# 01A-005.net
KiCad netlist of a schematic drawn in EAGLE
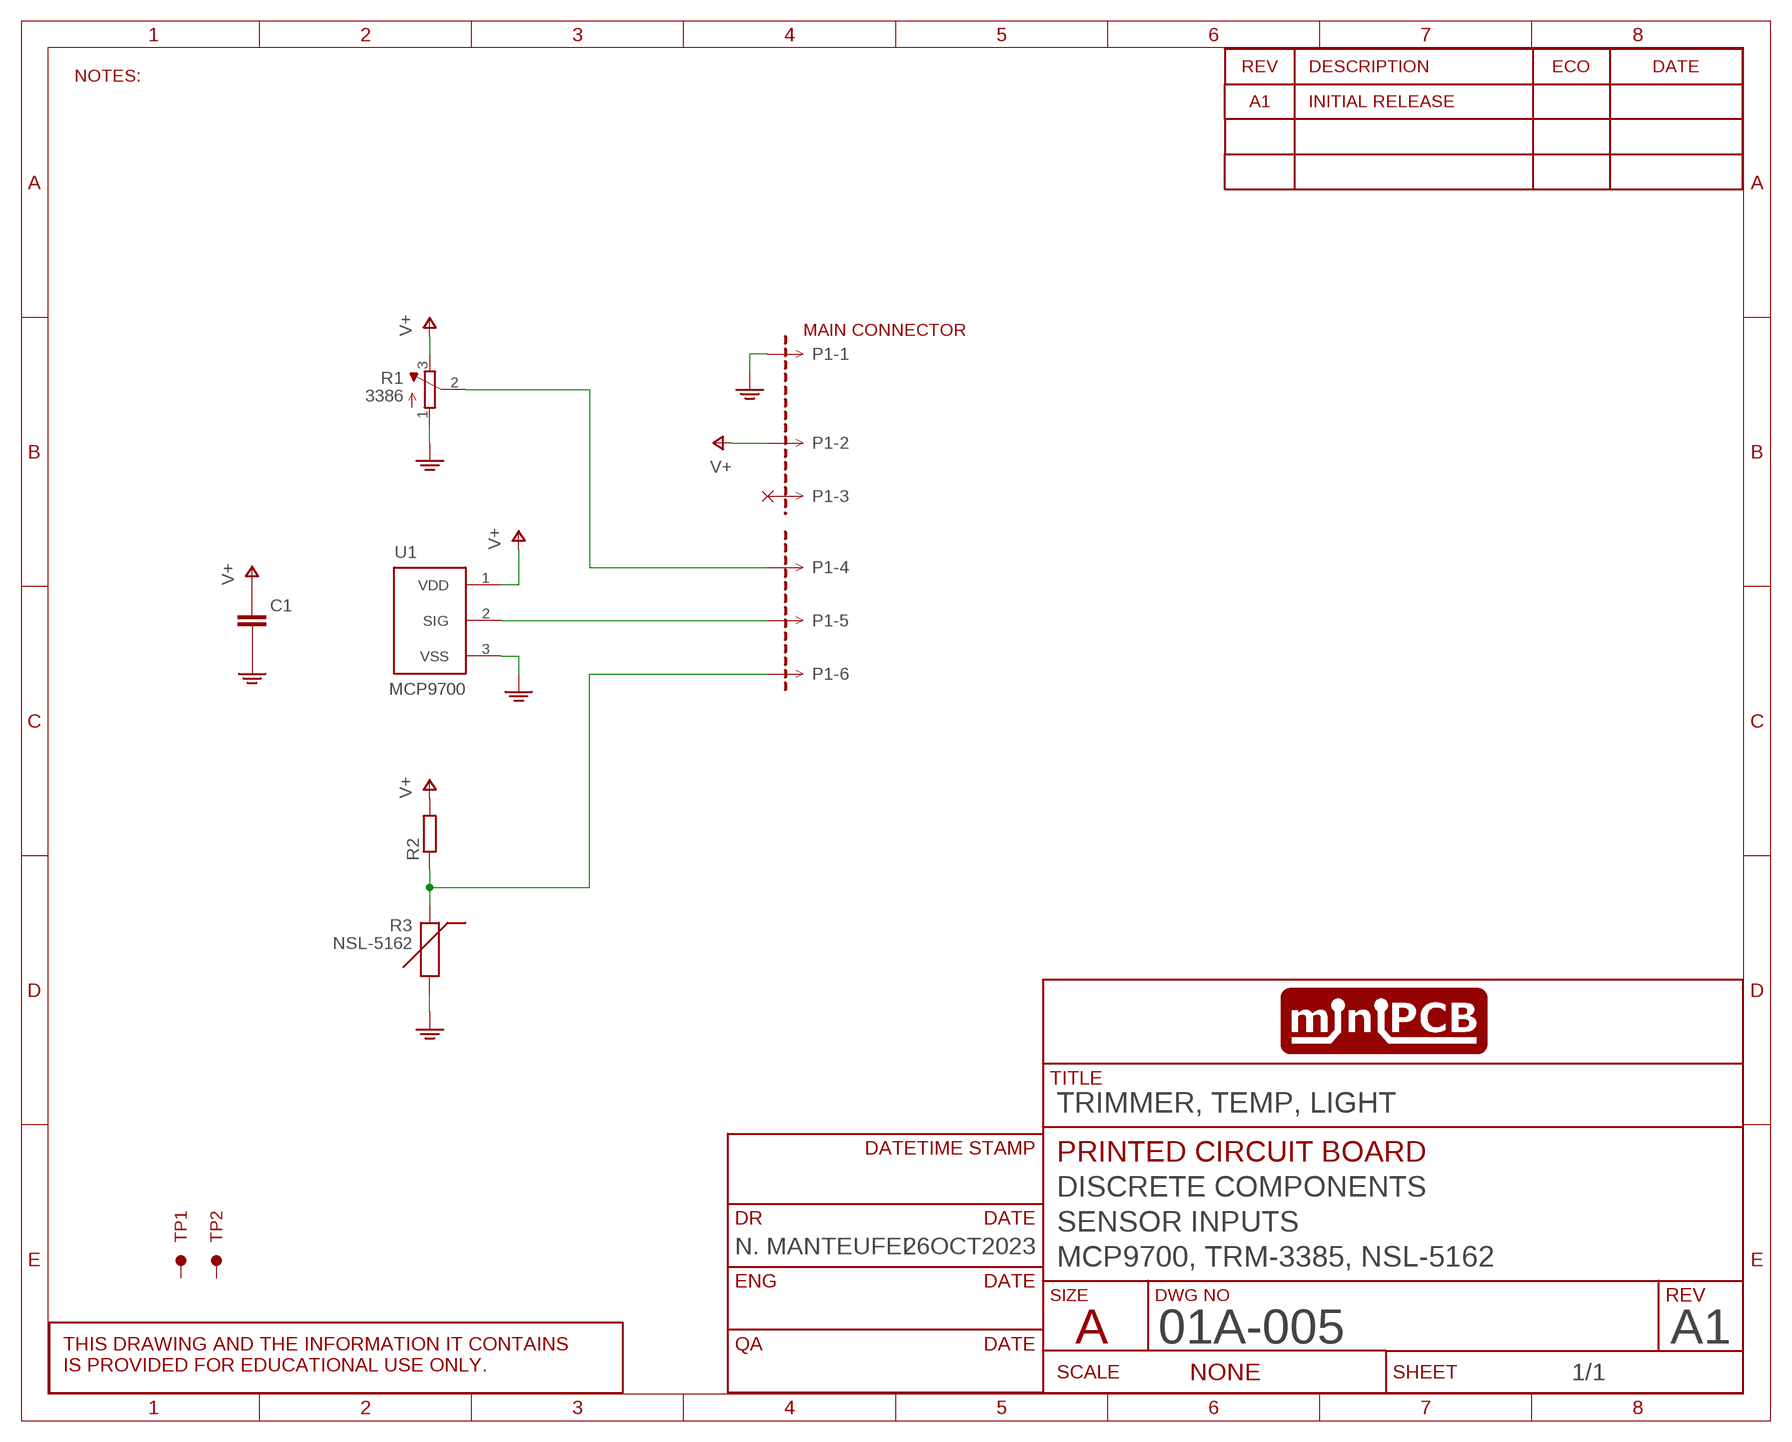
[diagram p0: schematic, sheet 1]

(export (version "E")
  (design (tool "Eeschema 10.0.6"))
  (components
    (comp (ref "C1")
      (value "CAPACITORSMD")
      (footprint "eagle-import:C0805")
      (libsource (lib "eagle-import") (part "CAPACITORSMD"))
    )
    (comp (ref "P1")
      (value "MINIPCB_6P")
      (footprint "eagle-import:PINS_6")
      (libsource (lib "eagle-import") (part "MINIPCB_6P"))
    )
    (comp (ref "PCB1")
      (value "MAIN CONNECTOR")
      (footprint "eagle-import:MINIPCB_00A_20X50")
      (fields
        (field (name "CIRCUIT_CATEGORY") "DISCRETE COMPONENTS")
        (field (name "PART_NUMBER") "01A-005")
        (field (name "REVISION") "A1-01")
        (field (name "TITLE") "SENSOR AFE")
      )
      (libsource (lib "eagle-import") (part "MINIPCB_0P00A-20X50"))
    )
    (comp (ref "R1")
      (value "3386")
      (footprint "eagle-import:TRIM-3386")
      (libsource (lib "eagle-import") (part "TRIMPOT3386"))
    )
    (comp (ref "R2")
      (value "RESISTORSMD")
      (footprint "eagle-import:R0805")
      (libsource (lib "eagle-import") (part "RESISTORSMD"))
    )
    (comp (ref "R3")
      (value "NSL-5162")
      (footprint "eagle-import:CERAMICPHOTOCELL")
      (libsource (lib "eagle-import") (part "CERAMICPHOTOCELL"))
    )
    (comp (ref "TP1")
      (value "TESTPOINTFIDUCIAL")
      (footprint "eagle-import:FIDUCIAL")
      (libsource (lib "eagle-import") (part "TESTPOINTFIDUCIAL"))
    )
    (comp (ref "TP2")
      (value "TESTPOINTFIDUCIAL")
      (footprint "eagle-import:FIDUCIAL")
      (libsource (lib "eagle-import") (part "TESTPOINTFIDUCIAL"))
    )
    (comp (ref "U1")
      (value "MCP9700")
      (footprint "eagle-import:SOT23")
      (libsource (lib "eagle-import") (part "MCP9700"))
    )
  )
  (nets
    (net (code "1") (name "GND") (class "Default")
      (node (ref "C1") (pin "2ASDF") (pinfunction "-_2ASDF") (pintype "passive"))
      (node (ref "P1") (pin "1") (pinfunction "1_1") (pintype "bidirectional"))
      (node (ref "R1") (pin "1") (pinfunction "A_1") (pintype "passive"))
      (node (ref "R3") (pin "P$2") (pinfunction "2_P$2") (pintype "bidirectional"))
      (node (ref "U1") (pin "3") (pinfunction "VSS_3") (pintype "bidirectional"))
    )
    (net (code "2") (name "Net-(P1D-1)") (class "Default")
      (node (ref "P1") (pin "4") (pinfunction "1_4") (pintype "bidirectional"))
      (node (ref "R1") (pin "2") (pinfunction "S_2") (pintype "passive"))
    )
    (net (code "3") (name "Net-(P1E-1)") (class "Default")
      (node (ref "P1") (pin "5") (pinfunction "1_5") (pintype "bidirectional"))
      (node (ref "U1") (pin "2") (pinfunction "SIG_2") (pintype "bidirectional"))
    )
    (net (code "4") (name "Net-(P1F-1)") (class "Default")
      (node (ref "P1") (pin "6") (pinfunction "1_6") (pintype "bidirectional"))
      (node (ref "R2") (pin "1") (pinfunction "1_1") (pintype "passive"))
      (node (ref "R3") (pin "P$1") (pinfunction "1_P$1") (pintype "bidirectional"))
    )
    (net (code "5") (name "V+") (class "Default")
      (node (ref "C1") (pin "1ASD") (pinfunction "+_1ASD") (pintype "passive"))
      (node (ref "P1") (pin "2") (pinfunction "1_2") (pintype "bidirectional"))
      (node (ref "R1") (pin "3") (pinfunction "E_3") (pintype "passive"))
      (node (ref "R2") (pin "2") (pinfunction "2_2") (pintype "passive"))
      (node (ref "U1") (pin "1") (pinfunction "VDD_1") (pintype "bidirectional"))
    )
    (net (code "6") (name "unconnected-(P1C-1-Pad3)") (class "Default")
      (node (ref "P1") (pin "3") (pinfunction "1_3") (pintype "bidirectional"))
    )
    (net (code "7") (name "unconnected-(TP1-1-PadFIDUCIAL)") (class "Default")
      (node (ref "TP1") (pin "FIDUCIAL") (pinfunction "1_FIDUCIAL") (pintype "bidirectional"))
    )
    (net (code "8") (name "unconnected-(TP2-1-PadFIDUCIAL)") (class "Default")
      (node (ref "TP2") (pin "FIDUCIAL") (pinfunction "1_FIDUCIAL") (pintype "bidirectional"))
    )
  )
)
